# MS5611.net
KiCad netlist of a schematic drawn in Altium Designer
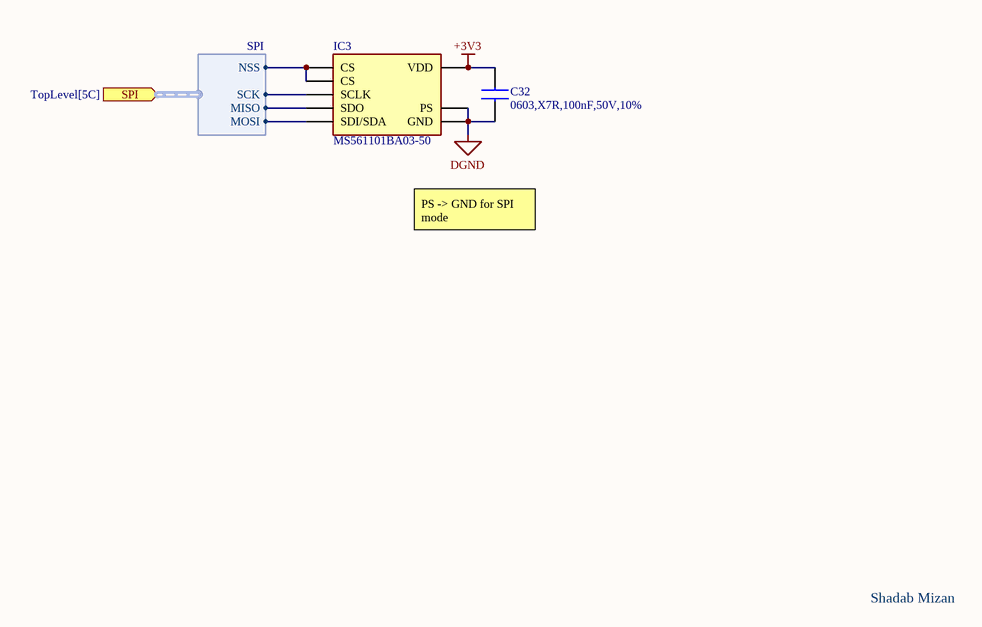
[diagram p0: MS5611.SchDoc]

(export (version "E")
  (design (tool "Eeschema 10.0.6"))
  (components
    (comp (ref "C32")
      (value "0603,X7R,100nF,50V,10%")
      (footprint "CAPC1608X90N")
      (description "50V 100nF X7R ±10% 0603 Multilayer Ceramic Capacitors MLCC - SMD/SMT ROHS")
      (fields (field (name "LCSC PART #") "C14663") (field (name "MANU PART #") "CC0603KRX7R9BB104"))
      (libsource (lib "flight-controller") (part "CC0603KRX7R9BB104"))
    )
    (comp (ref "IC3")
      (value "MS561101BA03-50")
      (footprint "MSI-MS561101BA03-50-8_V")
      (fields (field (name "LCSC PART #") "C15639"))
      (libsource (lib "flight-controller") (part "MS561101BA03-50"))
    )
  )
  (nets
    (net (code "2") (name "+3V3") (class "Default")
      (node (ref "C32") (pin "2") (pinfunction "2_2") (pintype "passive"))
      (node (ref "IC3") (pin "1") (pinfunction "VDD_1") (pintype "passive"))
    )
    (net (code "3") (name "/MISO") (class "Default")
      (node (ref "IC3") (pin "6") (pinfunction "SDO_6") (pintype "passive"))
    )
    (net (code "4") (name "/MOSI") (class "Default")
      (node (ref "IC3") (pin "7") (pinfunction "SDI/SDA_7") (pintype "passive"))
    )
    (net (code "5") (name "/NSS") (class "Default")
      (node (ref "IC3") (pin "4") (pinfunction "CS_4") (pintype "passive"))
      (node (ref "IC3") (pin "5") (pinfunction "CS_5") (pintype "passive"))
    )
    (net (code "6") (name "/SCK") (class "Default")
      (node (ref "IC3") (pin "8") (pinfunction "SCLK_8") (pintype "passive"))
    )
    (net (code "8") (name "DGND") (class "Default")
      (node (ref "C32") (pin "1") (pinfunction "1_1") (pintype "passive"))
      (node (ref "IC3") (pin "2") (pinfunction "PS_2") (pintype "passive"))
      (node (ref "IC3") (pin "3") (pinfunction "GND_3") (pintype "passive"))
    )
  )
)
